# Receiver.net
KiCad netlist of a schematic drawn in Altium Designer
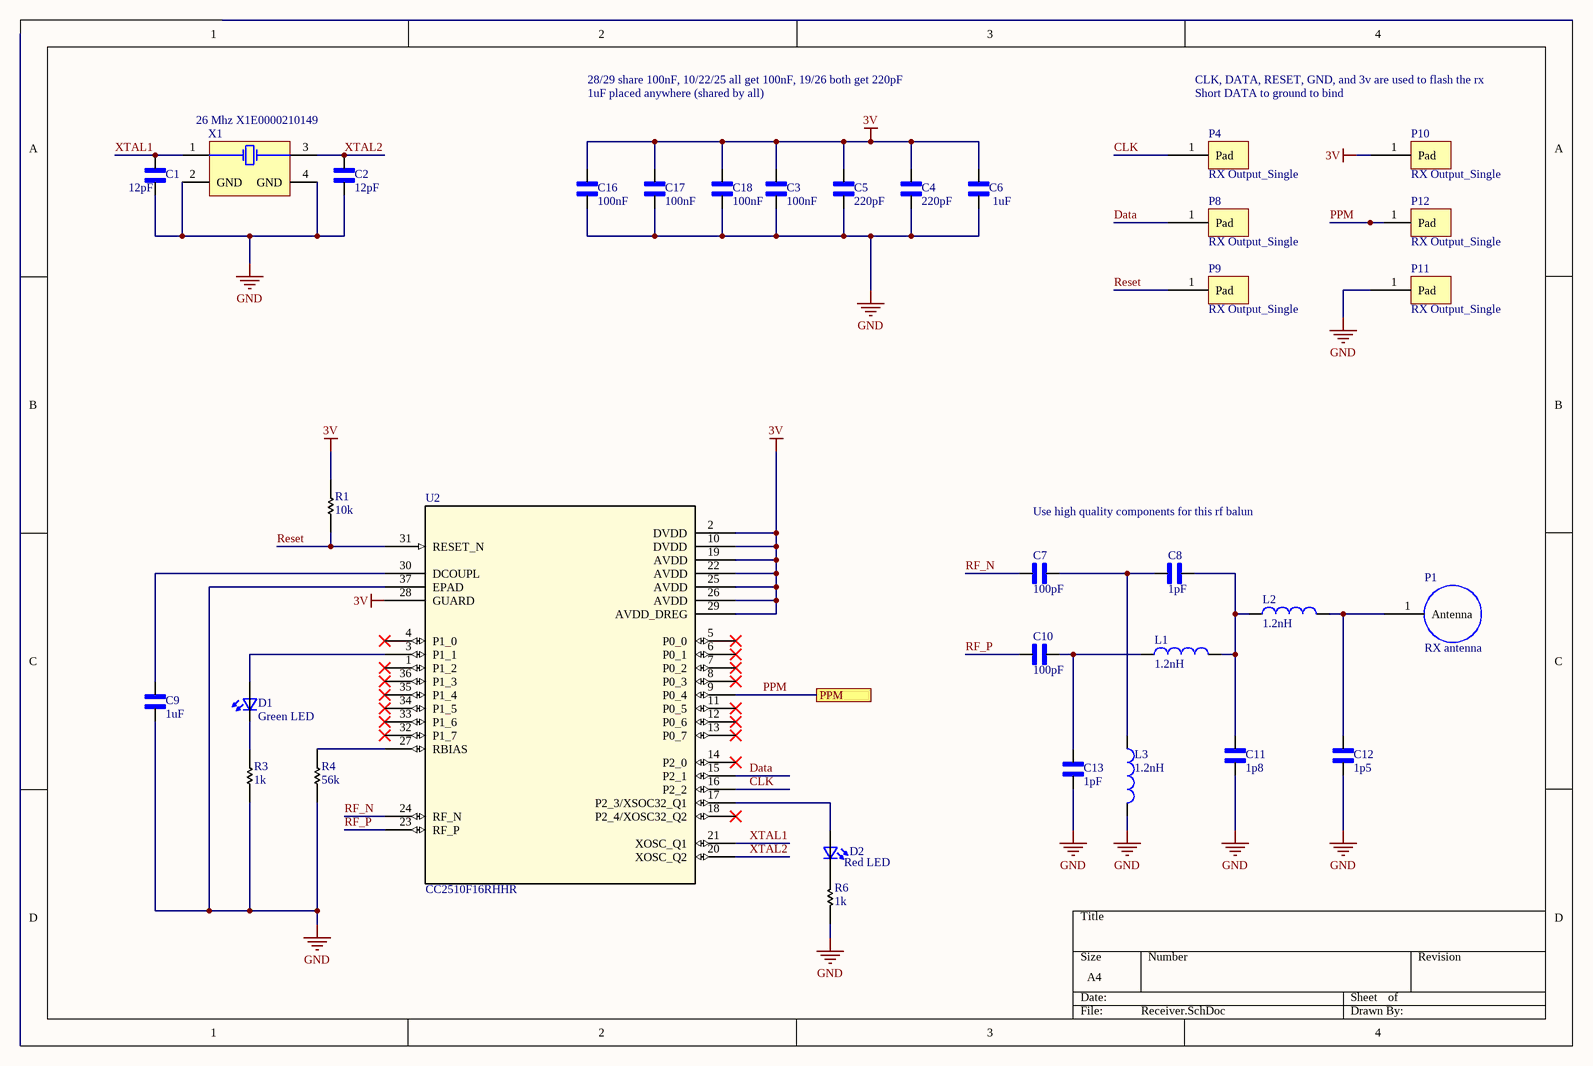
[diagram p0: Receiver.SchDoc]

(export (version "E")
  (design (tool "Eeschema 10.0.6"))
  (components
    (comp (ref "C1")
      (value "12pF")
      (footprint "0402 Capacitor Generic")
      (description "Generic 0402 Ceramic Capacitor")
      (fields (field (name "MP") "AC0402FR-071ML") (field (name "MF") "Yageo"))
      (libsource (lib "2Ch_Micro_Plane_lib") (part "0402 Ceramic Capacitor"))
    )
    (comp (ref "C2")
      (value "12pF")
      (footprint "0402 Capacitor Generic")
      (description "Generic 0402 Ceramic Capacitor")
      (fields (field (name "MP") "AC0402FR-071ML") (field (name "MF") "Yageo"))
      (libsource (lib "2Ch_Micro_Plane_lib") (part "0402 Ceramic Capacitor"))
    )
    (comp (ref "C3")
      (value "100nF")
      (footprint "0402 Capacitor Generic")
      (description "Generic 0402 Ceramic Capacitor")
      (fields (field (name "MP") "AC0402FR-071ML") (field (name "MF") "Yageo"))
      (libsource (lib "2Ch_Micro_Plane_lib") (part "0402 Ceramic Capacitor"))
    )
    (comp (ref "C4")
      (value "220pF")
      (footprint "0402 Capacitor Generic")
      (description "Generic 0402 Ceramic Capacitor")
      (fields (field (name "MP") "AC0402FR-071ML") (field (name "MF") "Yageo"))
      (libsource (lib "2Ch_Micro_Plane_lib") (part "0402 Ceramic Capacitor"))
    )
    (comp (ref "C5")
      (value "220pF")
      (footprint "0402 Capacitor Generic")
      (description "Generic 0402 Ceramic Capacitor")
      (fields (field (name "MP") "AC0402FR-071ML") (field (name "MF") "Yageo"))
      (libsource (lib "2Ch_Micro_Plane_lib") (part "0402 Ceramic Capacitor"))
    )
    (comp (ref "C6")
      (value "1uF")
      (footprint "0402 Capacitor Generic")
      (description "Generic 0402 Ceramic Capacitor")
      (fields (field (name "MP") "AC0402FR-071ML") (field (name "MF") "Yageo"))
      (libsource (lib "2Ch_Micro_Plane_lib") (part "0402 Ceramic Capacitor"))
    )
    (comp (ref "C7")
      (value "100pF")
      (footprint "0402 Capacitor Generic")
      (description "Generic 0402 Ceramic Capacitor")
      (fields (field (name "MP") "AC0402FR-071ML") (field (name "MF") "Yageo"))
      (libsource (lib "") (part "0402 Ceramic Capacitor_2"))
    )
    (comp (ref "C8")
      (value "1pF")
      (footprint "0402 Capacitor Generic")
      (description "Generic 0402 Ceramic Capacitor")
      (fields (field (name "MP") "AC0402FR-071ML") (field (name "MF") "Yageo"))
      (libsource (lib "") (part "0402 Ceramic Capacitor_1"))
    )
    (comp (ref "C9")
      (value "1uF")
      (footprint "0402 Capacitor Generic")
      (description "Generic 0402 Ceramic Capacitor")
      (fields (field (name "MP") "AC0402FR-071ML") (field (name "MF") "Yageo"))
      (libsource (lib "2Ch_Micro_Plane_lib") (part "0402 Ceramic Capacitor"))
    )
    (comp (ref "C10")
      (value "100pF")
      (footprint "0402 Capacitor Generic")
      (description "Generic 0402 Ceramic Capacitor")
      (fields (field (name "MP") "AC0402FR-071ML") (field (name "MF") "Yageo"))
      (libsource (lib "") (part "0402 Ceramic Capacitor_2"))
    )
    (comp (ref "C11")
      (value "1p8")
      (footprint "0402 Capacitor Generic")
      (description "Generic 0402 Ceramic Capacitor")
      (fields (field (name "MP") "AC0402FR-071ML") (field (name "MF") "Yageo"))
      (libsource (lib "2Ch_Micro_Plane_lib") (part "0402 Ceramic Capacitor"))
    )
    (comp (ref "C12")
      (value "1p5")
      (footprint "0402 Capacitor Generic")
      (description "Generic 0402 Ceramic Capacitor")
      (fields (field (name "MP") "AC0402FR-071ML") (field (name "MF") "Yageo"))
      (libsource (lib "2Ch_Micro_Plane_lib") (part "0402 Ceramic Capacitor"))
    )
    (comp (ref "C13")
      (value "1pF")
      (footprint "0402 Capacitor Generic")
      (description "Generic 0402 Ceramic Capacitor")
      (fields (field (name "MP") "AC0402FR-071ML") (field (name "MF") "Yageo"))
      (libsource (lib "2Ch_Micro_Plane_lib") (part "0402 Ceramic Capacitor"))
    )
    (comp (ref "C16")
      (value "100nF")
      (footprint "0402 Capacitor Generic")
      (description "Generic 0402 Ceramic Capacitor")
      (fields (field (name "MP") "AC0402FR-071ML") (field (name "MF") "Yageo"))
      (libsource (lib "2Ch_Micro_Plane_lib") (part "0402 Ceramic Capacitor"))
    )
    (comp (ref "C17")
      (value "100nF")
      (footprint "0402 Capacitor Generic")
      (description "Generic 0402 Ceramic Capacitor")
      (fields (field (name "MP") "AC0402FR-071ML") (field (name "MF") "Yageo"))
      (libsource (lib "2Ch_Micro_Plane_lib") (part "0402 Ceramic Capacitor"))
    )
    (comp (ref "C18")
      (value "100nF")
      (footprint "0402 Capacitor Generic")
      (description "Generic 0402 Ceramic Capacitor")
      (fields (field (name "MP") "AC0402FR-071ML") (field (name "MF") "Yageo"))
      (libsource (lib "2Ch_Micro_Plane_lib") (part "0402 Ceramic Capacitor"))
    )
    (comp (ref "D1")
      (value "Green LED")
      (footprint "0402 LED Generic")
      (description "0402 Generic LED")
      (libsource (lib "2Ch_Micro_Plane_lib") (part "0402 Generic LED"))
    )
    (comp (ref "D2")
      (value "Red LED")
      (footprint "0402 LED Generic")
      (description "0402 Generic LED")
      (libsource (lib "2Ch_Micro_Plane_lib") (part "0402 Generic LED"))
    )
    (comp (ref "L1")
      (value "1.2nH")
      (footprint "0402 Inductor Generic")
      (description "0402 Generic Inductor")
      (libsource (lib "2Ch_Micro_Plane_lib") (part "0402 Generic Inductor"))
    )
    (comp (ref "L2")
      (value "1.2nH")
      (footprint "0402 Inductor Generic")
      (description "0402 Generic Inductor")
      (libsource (lib "2Ch_Micro_Plane_lib") (part "0402 Generic Inductor"))
    )
    (comp (ref "L3")
      (value "1.2nH")
      (footprint "0402 Inductor Generic")
      (description "0402 Generic Inductor")
      (libsource (lib "2Ch_Micro_Plane_lib") (part "0402 Generic Inductor"))
    )
    (comp (ref "P1")
      (value "RX antenna")
      (footprint "Antenna pad")
      (libsource (lib "2Ch_Micro_Plane_lib") (part "Generic Antenna"))
    )
    (comp (ref "P4")
      (value "RX Output_Single")
      (footprint "1 Solder Pad")
      (libsource (lib "2Ch_Micro_Plane_lib") (part "RX Output_Single"))
    )
    (comp (ref "P8")
      (value "RX Output_Single")
      (footprint "1 Solder Pad")
      (libsource (lib "2Ch_Micro_Plane_lib") (part "RX Output_Single"))
    )
    (comp (ref "P9")
      (value "RX Output_Single")
      (footprint "1 Solder Pad")
      (libsource (lib "2Ch_Micro_Plane_lib") (part "RX Output_Single"))
    )
    (comp (ref "P10")
      (value "RX Output_Single")
      (footprint "1 Solder Pad")
      (libsource (lib "2Ch_Micro_Plane_lib") (part "RX Output_Single"))
    )
    (comp (ref "P11")
      (value "RX Output_Single")
      (footprint "1 Solder Pad")
      (libsource (lib "2Ch_Micro_Plane_lib") (part "RX Output_Single"))
    )
    (comp (ref "P12")
      (value "RX Output_Single")
      (footprint "1 Solder Pad")
      (libsource (lib "2Ch_Micro_Plane_lib") (part "RX Output_Single"))
    )
    (comp (ref "R1")
      (value "10k")
      (footprint "0402 Resistor Generic")
      (description "Generic 0402 Resistor")
      (libsource (lib "2Ch_Micro_Plane_lib") (part "0402 Generic Resistor"))
    )
    (comp (ref "R3")
      (value "1k")
      (footprint "0402 Resistor Generic")
      (description "Generic 0402 Resistor")
      (libsource (lib "2Ch_Micro_Plane_lib") (part "0402 Generic Resistor"))
    )
    (comp (ref "R4")
      (value "56k")
      (footprint "0402 Resistor Generic")
      (description "Generic 0402 Resistor")
      (libsource (lib "2Ch_Micro_Plane_lib") (part "0402 Generic Resistor"))
    )
    (comp (ref "R6")
      (value "1k")
      (footprint "0402 Resistor Generic")
      (description "Generic 0402 Resistor")
      (libsource (lib "2Ch_Micro_Plane_lib") (part "0402 Generic Resistor"))
    )
    (comp (ref "U2")
      (value "CC2510F16RHHR")
      (footprint "CC2510F32RHHR")
      (description "VQFN-36 RF Transceiver ICs")
      (libsource (lib "MiniFrogFC_lib") (part "CC2510F16RHHR"))
    )
    (comp (ref "X1")
      (value "26 Mhz X1E0000210149")
      (footprint "TSX-3225")
      (description "26MHz ±10ppm 12pF 40Ω TSX-3225")
      (fields (field (name "MANUFACTURER") "Epson"))
      (libsource (lib "2Ch_Micro_Plane_lib") (part "X1E0000210149"))
    )
  )
  (nets
    (net (code "1") (name "/CLK") (class "Default")
      (node (ref "P4") (pin "1") (pinfunction "Pad_1") (pintype "passive"))
      (node (ref "U2") (pin "16") (pinfunction "P2_2_16") (pintype "bidirectional"))
    )
    (net (code "2") (name "/Data") (class "Default")
      (node (ref "P8") (pin "1") (pinfunction "Pad_1") (pintype "passive"))
      (node (ref "U2") (pin "15") (pinfunction "P2_1_15") (pintype "bidirectional"))
    )
    (net (code "3") (name "/PPM") (class "Default")
      (node (ref "P12") (pin "1") (pinfunction "Pad_1") (pintype "passive"))
      (node (ref "U2") (pin "9") (pinfunction "P0_4_9") (pintype "bidirectional"))
    )
    (net (code "4") (name "/RF_N") (class "Default")
      (node (ref "C7") (pin "2") (pinfunction "2_2") (pintype "passive"))
      (node (ref "U2") (pin "24") (pinfunction "RF_N_24") (pintype "bidirectional"))
    )
    (net (code "5") (name "/RF_P") (class "Default")
      (node (ref "C10") (pin "2") (pinfunction "2_2") (pintype "passive"))
      (node (ref "U2") (pin "23") (pinfunction "RF_P_23") (pintype "bidirectional"))
    )
    (net (code "6") (name "/Reset") (class "Default")
      (node (ref "P9") (pin "1") (pinfunction "Pad_1") (pintype "passive"))
      (node (ref "R1") (pin "2") (pinfunction "2_2") (pintype "passive"))
      (node (ref "U2") (pin "31") (pinfunction "RESET_N_31") (pintype "input"))
    )
    (net (code "7") (name "/XTAL1") (class "Default")
      (node (ref "C1") (pin "1") (pinfunction "1_1") (pintype "passive"))
      (node (ref "U2") (pin "21") (pinfunction "XOSC_Q1_21") (pintype "bidirectional"))
      (node (ref "X1") (pin "1") (pinfunction "X1_1") (pintype "passive"))
    )
    (net (code "8") (name "/XTAL2") (class "Default")
      (node (ref "C2") (pin "1") (pinfunction "1_1") (pintype "passive"))
      (node (ref "U2") (pin "20") (pinfunction "XOSC_Q2_20") (pintype "bidirectional"))
      (node (ref "X1") (pin "3") (pinfunction "X2_3") (pintype "passive"))
    )
    (net (code "9") (name "3V") (class "Default")
      (node (ref "C16") (pin "1") (pinfunction "1_1") (pintype "passive"))
      (node (ref "C17") (pin "1") (pinfunction "1_1") (pintype "passive"))
      (node (ref "C18") (pin "1") (pinfunction "1_1") (pintype "passive"))
      (node (ref "C3") (pin "1") (pinfunction "1_1") (pintype "passive"))
      (node (ref "C4") (pin "1") (pinfunction "1_1") (pintype "passive"))
      (node (ref "C5") (pin "1") (pinfunction "1_1") (pintype "passive"))
      (node (ref "C6") (pin "1") (pinfunction "1_1") (pintype "passive"))
      (node (ref "P10") (pin "1") (pinfunction "Pad_1") (pintype "passive"))
      (node (ref "R1") (pin "1") (pinfunction "1_1") (pintype "passive"))
      (node (ref "U2") (pin "10") (pinfunction "DVDD_10") (pintype "passive"))
      (node (ref "U2") (pin "19") (pinfunction "AVDD_19") (pintype "passive"))
      (node (ref "U2") (pin "2") (pinfunction "DVDD_2") (pintype "passive"))
      (node (ref "U2") (pin "22") (pinfunction "AVDD_22") (pintype "passive"))
      (node (ref "U2") (pin "25") (pinfunction "AVDD_25") (pintype "passive"))
      (node (ref "U2") (pin "26") (pinfunction "AVDD_26") (pintype "passive"))
      (node (ref "U2") (pin "28") (pinfunction "GUARD_28") (pintype "passive"))
      (node (ref "U2") (pin "29") (pinfunction "AVDD_DREG_29") (pintype "passive"))
    )
    (net (code "10") (name "GND") (class "Default")
      (node (ref "C1") (pin "2") (pinfunction "2_2") (pintype "passive"))
      (node (ref "C11") (pin "2") (pinfunction "2_2") (pintype "passive"))
      (node (ref "C12") (pin "2") (pinfunction "2_2") (pintype "passive"))
      (node (ref "C13") (pin "2") (pinfunction "2_2") (pintype "passive"))
      (node (ref "C16") (pin "2") (pinfunction "2_2") (pintype "passive"))
      (node (ref "C17") (pin "2") (pinfunction "2_2") (pintype "passive"))
      (node (ref "C18") (pin "2") (pinfunction "2_2") (pintype "passive"))
      (node (ref "C2") (pin "2") (pinfunction "2_2") (pintype "passive"))
      (node (ref "C3") (pin "2") (pinfunction "2_2") (pintype "passive"))
      (node (ref "C4") (pin "2") (pinfunction "2_2") (pintype "passive"))
      (node (ref "C5") (pin "2") (pinfunction "2_2") (pintype "passive"))
      (node (ref "C6") (pin "2") (pinfunction "2_2") (pintype "passive"))
      (node (ref "C9") (pin "2") (pinfunction "2_2") (pintype "passive"))
      (node (ref "L3") (pin "2") (pinfunction "2_2") (pintype "passive"))
      (node (ref "P11") (pin "1") (pinfunction "Pad_1") (pintype "passive"))
      (node (ref "R3") (pin "2") (pinfunction "2_2") (pintype "passive"))
      (node (ref "R4") (pin "2") (pinfunction "2_2") (pintype "passive"))
      (node (ref "R6") (pin "2") (pinfunction "2_2") (pintype "passive"))
      (node (ref "U2") (pin "37") (pinfunction "EPAD_37") (pintype "passive"))
      (node (ref "X1") (pin "2") (pinfunction "GND_2") (pintype "power_in"))
      (node (ref "X1") (pin "4") (pinfunction "GND_4") (pintype "power_in"))
    )
    (net (code "11") (name "Net-(C7-Pad1)") (class "Default")
      (node (ref "C7") (pin "1") (pinfunction "1_1") (pintype "passive"))
      (node (ref "C8") (pin "1") (pinfunction "1_1") (pintype "passive"))
      (node (ref "L3") (pin "1") (pinfunction "1_1") (pintype "passive"))
    )
    (net (code "12") (name "Net-(C10-Pad1)") (class "Default")
      (node (ref "C10") (pin "1") (pinfunction "1_1") (pintype "passive"))
      (node (ref "C13") (pin "1") (pinfunction "1_1") (pintype "passive"))
      (node (ref "L1") (pin "1") (pinfunction "1_1") (pintype "passive"))
    )
    (net (code "13") (name "Net-(C11-Pad1)") (class "Default")
      (node (ref "C11") (pin "1") (pinfunction "1_1") (pintype "passive"))
      (node (ref "C8") (pin "2") (pinfunction "2_2") (pintype "passive"))
      (node (ref "L1") (pin "2") (pinfunction "2_2") (pintype "passive"))
      (node (ref "L2") (pin "1") (pinfunction "1_1") (pintype "passive"))
    )
    (net (code "14") (name "Net-(D1-A2)") (class "Default")
      (node (ref "D1") (pin "2") (pinfunction "A2_2") (pintype "passive"))
      (node (ref "U2") (pin "3") (pinfunction "P1_1_3") (pintype "bidirectional"))
    )
    (net (code "15") (name "Net-(D1-K2)") (class "Default")
      (node (ref "D1") (pin "1") (pinfunction "K2_1") (pintype "passive"))
      (node (ref "R3") (pin "1") (pinfunction "1_1") (pintype "passive"))
    )
    (net (code "16") (name "Net-(D2-A2)") (class "Default")
      (node (ref "D2") (pin "2") (pinfunction "A2_2") (pintype "passive"))
      (node (ref "U2") (pin "17") (pinfunction "P2_3/XSOC32_Q1_17") (pintype "bidirectional"))
    )
    (net (code "17") (name "Net-(D2-K2)") (class "Default")
      (node (ref "D2") (pin "1") (pinfunction "K2_1") (pintype "passive"))
      (node (ref "R6") (pin "1") (pinfunction "1_1") (pintype "passive"))
    )
    (net (code "18") (name "Net-(P1-Antenna)") (class "Default")
      (node (ref "C12") (pin "1") (pinfunction "1_1") (pintype "passive"))
      (node (ref "L2") (pin "2") (pinfunction "2_2") (pintype "passive"))
      (node (ref "P1") (pin "1") (pinfunction "Antenna_1") (pintype "passive"))
    )
    (net (code "19") (name "Net-(U2-DCOUPL)") (class "Default")
      (node (ref "C9") (pin "1") (pinfunction "1_1") (pintype "passive"))
      (node (ref "U2") (pin "30") (pinfunction "DCOUPL_30") (pintype "passive"))
    )
    (net (code "20") (name "Net-(U2-RBIAS)") (class "Default")
      (node (ref "R4") (pin "1") (pinfunction "1_1") (pintype "passive"))
      (node (ref "U2") (pin "27") (pinfunction "RBIAS_27") (pintype "bidirectional"))
    )
    (net (code "21") (name "unconnected-(U2-P0_0-Pad5)") (class "Default")
      (node (ref "U2") (pin "5") (pinfunction "P0_0_5") (pintype "bidirectional+no_connect"))
    )
    (net (code "22") (name "unconnected-(U2-P0_1-Pad6)") (class "Default")
      (node (ref "U2") (pin "6") (pinfunction "P0_1_6") (pintype "bidirectional+no_connect"))
    )
    (net (code "23") (name "unconnected-(U2-P0_2-Pad7)") (class "Default")
      (node (ref "U2") (pin "7") (pinfunction "P0_2_7") (pintype "bidirectional+no_connect"))
    )
    (net (code "24") (name "unconnected-(U2-P0_3-Pad8)") (class "Default")
      (node (ref "U2") (pin "8") (pinfunction "P0_3_8") (pintype "bidirectional+no_connect"))
    )
    (net (code "25") (name "unconnected-(U2-P0_5-Pad11)") (class "Default")
      (node (ref "U2") (pin "11") (pinfunction "P0_5_11") (pintype "bidirectional+no_connect"))
    )
    (net (code "26") (name "unconnected-(U2-P0_6-Pad12)") (class "Default")
      (node (ref "U2") (pin "12") (pinfunction "P0_6_12") (pintype "bidirectional+no_connect"))
    )
    (net (code "27") (name "unconnected-(U2-P0_7-Pad13)") (class "Default")
      (node (ref "U2") (pin "13") (pinfunction "P0_7_13") (pintype "bidirectional+no_connect"))
    )
    (net (code "28") (name "unconnected-(U2-P1_0-Pad4)") (class "Default")
      (node (ref "U2") (pin "4") (pinfunction "P1_0_4") (pintype "bidirectional+no_connect"))
    )
    (net (code "29") (name "unconnected-(U2-P1_2-Pad1)") (class "Default")
      (node (ref "U2") (pin "1") (pinfunction "P1_2_1") (pintype "bidirectional+no_connect"))
    )
    (net (code "30") (name "unconnected-(U2-P1_3-Pad36)") (class "Default")
      (node (ref "U2") (pin "36") (pinfunction "P1_3_36") (pintype "bidirectional+no_connect"))
    )
    (net (code "31") (name "unconnected-(U2-P1_4-Pad35)") (class "Default")
      (node (ref "U2") (pin "35") (pinfunction "P1_4_35") (pintype "bidirectional+no_connect"))
    )
    (net (code "32") (name "unconnected-(U2-P1_5-Pad34)") (class "Default")
      (node (ref "U2") (pin "34") (pinfunction "P1_5_34") (pintype "bidirectional+no_connect"))
    )
    (net (code "33") (name "unconnected-(U2-P1_6-Pad33)") (class "Default")
      (node (ref "U2") (pin "33") (pinfunction "P1_6_33") (pintype "bidirectional+no_connect"))
    )
    (net (code "34") (name "unconnected-(U2-P1_7-Pad32)") (class "Default")
      (node (ref "U2") (pin "32") (pinfunction "P1_7_32") (pintype "bidirectional+no_connect"))
    )
    (net (code "35") (name "unconnected-(U2-P2_0-Pad14)") (class "Default")
      (node (ref "U2") (pin "14") (pinfunction "P2_0_14") (pintype "bidirectional+no_connect"))
    )
    (net (code "36") (name "unconnected-(U2-P2_4{slash}XOSC32_Q2-Pad18)") (class "Default")
      (node (ref "U2") (pin "18") (pinfunction "P2_4/XOSC32_Q2_18") (pintype "bidirectional+no_connect"))
    )
  )
)
